# 3_-MCU.net
KiCad netlist of a schematic drawn in Altium Designer
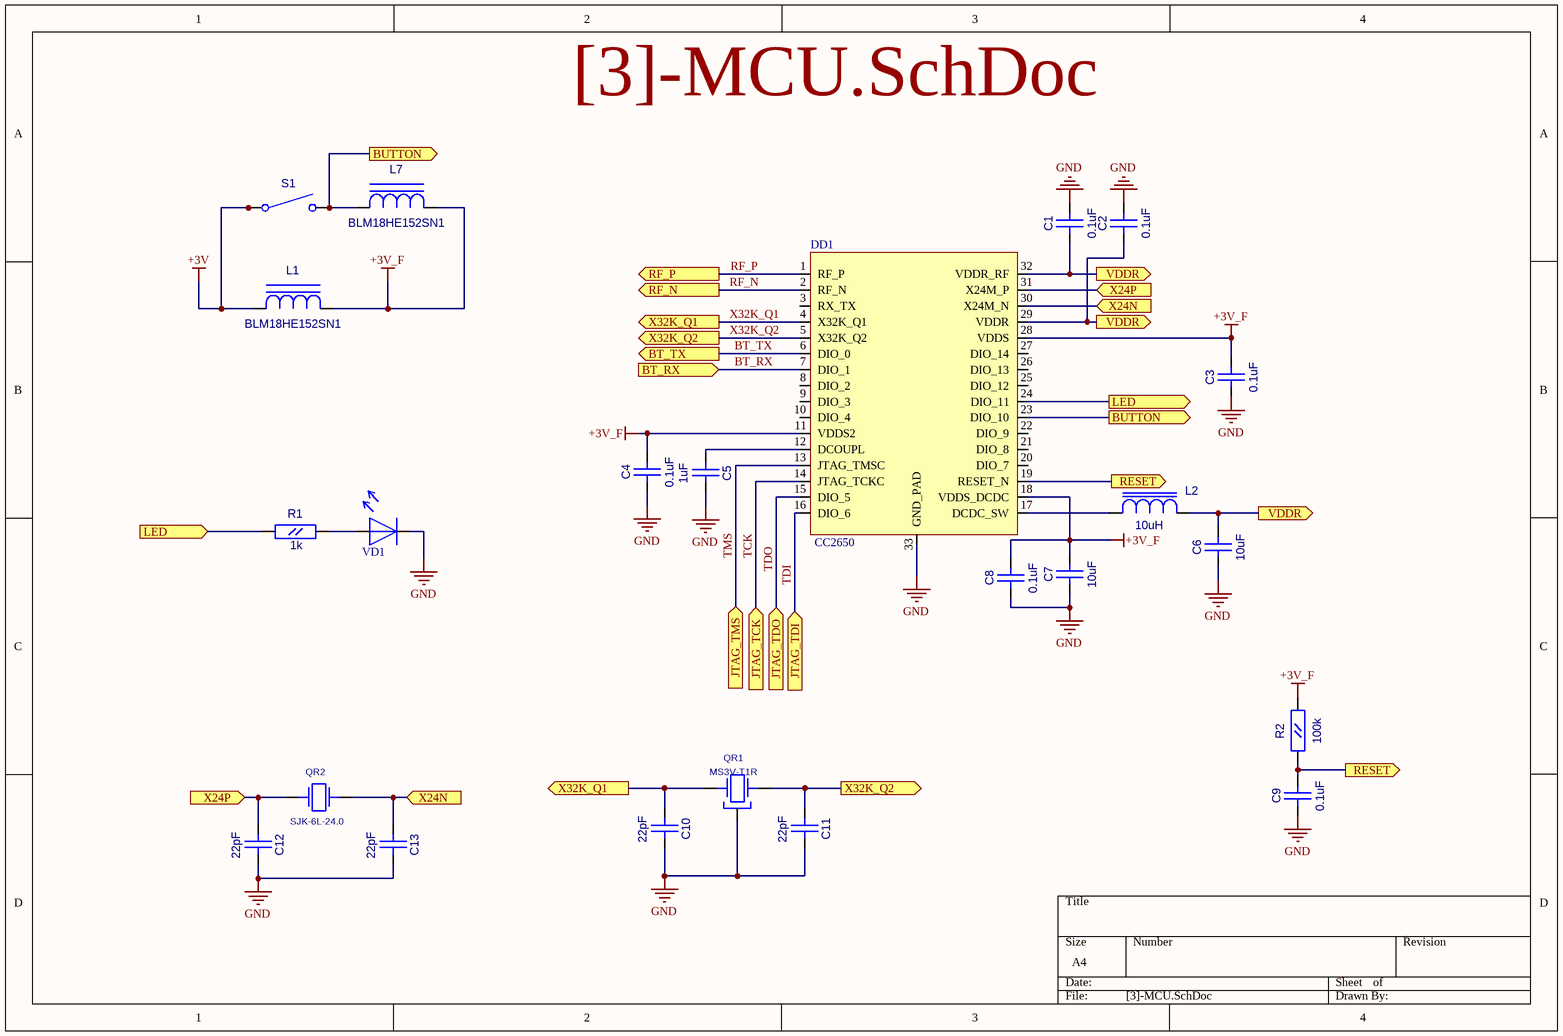
[diagram p0: [3]-MCU.SchDoc]

(export (version "E")
  (design (tool "Eeschema 10.0.6"))
  (components
    (comp (ref "C1")
      (value "0.1uF")
      (footprint "CC0603")
      (description "CC0603")
      (libsource (lib "gprs_modem_2") (part "CC0603"))
    )
    (comp (ref "C2")
      (value "0.1uF")
      (footprint "CC0603")
      (description "CC0603")
      (libsource (lib "gprs_modem_2") (part "CC0603"))
    )
    (comp (ref "C3")
      (value "0.1uF")
      (footprint "CC0603")
      (description "CC0603")
      (libsource (lib "gprs_modem_2") (part "CC0603"))
    )
    (comp (ref "C4")
      (value "0.1uF")
      (footprint "CC0603")
      (description "CC0603")
      (libsource (lib "gprs_modem_2") (part "CC0603"))
    )
    (comp (ref "C5")
      (value "1uF")
      (footprint "CC0603")
      (description "CC0603")
      (libsource (lib "gprs_modem_2") (part "CC0603"))
    )
    (comp (ref "C6")
      (value "10uF")
      (footprint "CC0805")
      (description "CC0805")
      (libsource (lib "gprs_modem_2") (part "CC0805"))
    )
    (comp (ref "C7")
      (value "10uF")
      (footprint "CC0805")
      (description "CC0805")
      (libsource (lib "gprs_modem_2") (part "CC0805"))
    )
    (comp (ref "C8")
      (value "0.1uF")
      (footprint "CC0603")
      (description "CC0603")
      (libsource (lib "gprs_modem_2") (part "CC0603"))
    )
    (comp (ref "C9")
      (value "0.1uF")
      (footprint "CC0603")
      (description "CC0603")
      (libsource (lib "gprs_modem_2") (part "CC0603"))
    )
    (comp (ref "C10")
      (value "22pF")
      (footprint "CC0603")
      (description "CC0603")
      (libsource (lib "gprs_modem_2") (part "CC0603"))
    )
    (comp (ref "C11")
      (value "22pF")
      (footprint "CC0603")
      (description "CC0603")
      (libsource (lib "gprs_modem_2") (part "CC0603"))
    )
    (comp (ref "C12")
      (value "22pF")
      (footprint "CC0603")
      (description "CC0603")
      (libsource (lib "gprs_modem_2") (part "CC0603"))
    )
    (comp (ref "C13")
      (value "22pF")
      (footprint "CC0603")
      (description "CC0603")
      (libsource (lib "gprs_modem_2") (part "CC0603"))
    )
    (comp (ref "DD1")
      (value "CC2650")
      (footprint "QFN32_TI")
      (description "CC2650RHBT")
      (libsource (lib "gprs_modem_2") (part "CC2650RHB"))
    )
    (comp (ref "L1")
      (value "BLM18HE152SN1")
      (footprint "L0603")
      (description "L0603")
      (libsource (lib "gprs_modem_2") (part "L0603"))
    )
    (comp (ref "L2")
      (value "10uH")
      (footprint "RC0805")
      (description "L0805")
      (libsource (lib "gprs_modem_2") (part "L0805"))
    )
    (comp (ref "L7")
      (value "BLM18HE152SN1")
      (footprint "L0603")
      (description "L0603")
      (libsource (lib "gprs_modem_2") (part "L0603"))
    )
    (comp (ref "QR1")
      (value "MS3V-T1R")
      (footprint "MS3V-T1R")
      (description "CRYSTAL_32768 Hz")
      (libsource (lib "gprs_modem_2") (part "MS3V-T1R"))
    )
    (comp (ref "QR2")
      (value "SJK-6L-24.0")
      (footprint "AC5032_2")
      (description "AC5032/2")
      (libsource (lib "gprs_modem_2") (part "AC5032_2"))
    )
    (comp (ref "R1")
      (value "1k")
      (footprint "RC0603")
      (description "RC0603")
      (libsource (lib "fizik_lib") (part "RC0603"))
    )
    (comp (ref "R2")
      (value "100k")
      (footprint "RC0603")
      (description "RC0603")
      (libsource (lib "gprs_modem_2") (part "RC0603"))
    )
    (comp (ref "S1")
      (value "IT-1147")
      (footprint "IT-1147")
      (description "Switch, Single Pole, Single Throw, Normally Open")
      (libsource (lib "fizik_lib") (part "IT-1147"))
    )
    (comp (ref "VD1")
      (value "LED_0805")
      (footprint "LED0805")
      (libsource (lib "fizik_lib") (part "LED_0805"))
    )
  )
  (nets
    (net (code "1") (name "+3V") (class "Default")
      (node (ref "L1") (pin "1") (pinfunction "A_1") (pintype "passive"))
      (node (ref "S1") (pin "1") (pinfunction "C1_1") (pintype "passive"))
      (node (ref "S1") (pin "2") (pintype "passive"))
    )
    (net (code "2") (name "+3V_F") (class "Default")
      (node (ref "C3") (pin "2") (pinfunction "B_2") (pintype "passive"))
      (node (ref "C4") (pin "2") (pinfunction "B_2") (pintype "passive"))
      (node (ref "C7") (pin "2") (pinfunction "B_2") (pintype "passive"))
      (node (ref "C8") (pin "2") (pinfunction "B_2") (pintype "passive"))
      (node (ref "DD1") (pin "11") (pinfunction "VDDS2_11") (pintype "passive"))
      (node (ref "DD1") (pin "18") (pinfunction "VDDS_DCDC_18") (pintype "passive"))
      (node (ref "DD1") (pin "28") (pinfunction "VDDS_28") (pintype "passive"))
      (node (ref "L1") (pin "2") (pinfunction "C_2") (pintype "passive"))
      (node (ref "L7") (pin "2") (pinfunction "C_2") (pintype "passive"))
      (node (ref "R2") (pin "2") (pinfunction "B_2") (pintype "passive"))
    )
    (net (code "3") (name "/BT_RX") (class "Default")
      (node (ref "DD1") (pin "7") (pinfunction "DIO_1_7") (pintype "passive"))
    )
    (net (code "4") (name "/BT_TX") (class "Default")
      (node (ref "DD1") (pin "6") (pinfunction "DIO_0_6") (pintype "passive"))
    )
    (net (code "5") (name "/BUTTON") (class "Default")
      (node (ref "DD1") (pin "23") (pinfunction "DIO_10_23") (pintype "passive"))
      (node (ref "L7") (pin "1") (pinfunction "A_1") (pintype "passive"))
      (node (ref "S1") (pin "3") (pinfunction "C2_3") (pintype "passive"))
      (node (ref "S1") (pin "4") (pintype "passive"))
    )
    (net (code "6") (name "/LED") (class "Default")
      (node (ref "DD1") (pin "24") (pinfunction "DIO_11_24") (pintype "passive"))
      (node (ref "R1") (pin "1") (pinfunction "A_1") (pintype "passive"))
    )
    (net (code "7") (name "/RESET") (class "Default")
      (node (ref "C9") (pin "2") (pinfunction "B_2") (pintype "passive"))
      (node (ref "DD1") (pin "19") (pinfunction "RESET_N_19") (pintype "passive"))
      (node (ref "R2") (pin "1") (pinfunction "A_1") (pintype "passive"))
    )
    (net (code "8") (name "/RF_N") (class "Default")
      (node (ref "DD1") (pin "2") (pinfunction "RF_N_2") (pintype "passive"))
    )
    (net (code "9") (name "/RF_P") (class "Default")
      (node (ref "DD1") (pin "1") (pinfunction "RF_P_1") (pintype "passive"))
    )
    (net (code "10") (name "/TCK") (class "Default")
      (node (ref "DD1") (pin "14") (pinfunction "JTAG_TCKC_14") (pintype "passive"))
    )
    (net (code "11") (name "/TDI") (class "Default")
      (node (ref "DD1") (pin "16") (pinfunction "DIO_6_16") (pintype "passive"))
    )
    (net (code "12") (name "/TDO") (class "Default")
      (node (ref "DD1") (pin "15") (pinfunction "DIO_5_15") (pintype "passive"))
    )
    (net (code "13") (name "/TMS") (class "Default")
      (node (ref "DD1") (pin "13") (pinfunction "JTAG_TMSC_13") (pintype "passive"))
    )
    (net (code "14") (name "/VDDR") (class "Default")
      (node (ref "C1") (pin "1") (pinfunction "A_1") (pintype "passive"))
      (node (ref "C2") (pin "1") (pinfunction "A_1") (pintype "passive"))
      (node (ref "C6") (pin "2") (pinfunction "B_2") (pintype "passive"))
      (node (ref "DD1") (pin "29") (pinfunction "VDDR_29") (pintype "passive"))
      (node (ref "DD1") (pin "32") (pinfunction "VDDR_RF_32") (pintype "passive"))
      (node (ref "L2") (pin "2") (pinfunction "B_2") (pintype "passive"))
    )
    (net (code "15") (name "/X24N") (class "Default")
      (node (ref "C13") (pin "1") (pinfunction "A_1") (pintype "passive"))
      (node (ref "DD1") (pin "30") (pinfunction "X24M_N_30") (pintype "passive"))
      (node (ref "QR2") (pin "2") (pintype "passive"))
    )
    (net (code "16") (name "/X24P") (class "Default")
      (node (ref "C12") (pin "1") (pinfunction "A_1") (pintype "passive"))
      (node (ref "DD1") (pin "31") (pinfunction "X24M_P_31") (pintype "passive"))
      (node (ref "QR2") (pin "1") (pintype "passive"))
    )
    (net (code "17") (name "/X32K_Q1") (class "Default")
      (node (ref "C10") (pin "1") (pinfunction "A_1") (pintype "passive"))
      (node (ref "DD1") (pin "4") (pinfunction "X32K_Q1_4") (pintype "passive"))
      (node (ref "QR1") (pin "2") (pinfunction "X2_2") (pintype "passive"))
    )
    (net (code "18") (name "/X32K_Q2") (class "Default")
      (node (ref "C11") (pin "1") (pinfunction "A_1") (pintype "passive"))
      (node (ref "DD1") (pin "5") (pinfunction "X32K_Q2_5") (pintype "passive"))
      (node (ref "QR1") (pin "1") (pinfunction "X1_1") (pintype "passive"))
    )
    (net (code "19") (name "GND") (class "Default")
      (node (ref "C1") (pin "2") (pinfunction "B_2") (pintype "passive"))
      (node (ref "C10") (pin "2") (pinfunction "B_2") (pintype "passive"))
      (node (ref "C11") (pin "2") (pinfunction "B_2") (pintype "passive"))
      (node (ref "C12") (pin "2") (pinfunction "B_2") (pintype "passive"))
      (node (ref "C13") (pin "2") (pinfunction "B_2") (pintype "passive"))
      (node (ref "C2") (pin "2") (pinfunction "B_2") (pintype "passive"))
      (node (ref "C3") (pin "1") (pinfunction "A_1") (pintype "passive"))
      (node (ref "C4") (pin "1") (pinfunction "A_1") (pintype "passive"))
      (node (ref "C5") (pin "2") (pinfunction "B_2") (pintype "passive"))
      (node (ref "C6") (pin "1") (pinfunction "A_1") (pintype "passive"))
      (node (ref "C7") (pin "1") (pinfunction "A_1") (pintype "passive"))
      (node (ref "C8") (pin "1") (pinfunction "A_1") (pintype "passive"))
      (node (ref "C9") (pin "1") (pinfunction "A_1") (pintype "passive"))
      (node (ref "DD1") (pin "33") (pinfunction "GND_PAD_33") (pintype "passive"))
      (node (ref "QR1") (pin "3") (pinfunction "3_3") (pintype "passive"))
      (node (ref "VD1") (pin "2") (pintype "passive"))
    )
    (net (code "20") (name "Net-(C5-A)") (class "Default")
      (node (ref "C5") (pin "1") (pinfunction "A_1") (pintype "passive"))
      (node (ref "DD1") (pin "12") (pinfunction "DCOUPL_12") (pintype "passive"))
    )
    (net (code "21") (name "Net-(DD1-DCDC_SW)") (class "Default")
      (node (ref "DD1") (pin "17") (pinfunction "DCDC_SW_17") (pintype "passive"))
      (node (ref "L2") (pin "1") (pinfunction "A_1") (pintype "passive"))
    )
    (net (code "22") (name "Net-(R1-B)") (class "Default")
      (node (ref "R1") (pin "2") (pinfunction "B_2") (pintype "passive"))
      (node (ref "VD1") (pin "1") (pintype "passive"))
    )
    (net (code "23") (name "unconnected-(DD1-DIO_2-Pad8)") (class "Default")
      (node (ref "DD1") (pin "8") (pinfunction "DIO_2_8") (pintype "passive"))
    )
    (net (code "24") (name "unconnected-(DD1-DIO_3-Pad9)") (class "Default")
      (node (ref "DD1") (pin "9") (pinfunction "DIO_3_9") (pintype "passive"))
    )
    (net (code "25") (name "unconnected-(DD1-DIO_4-Pad10)") (class "Default")
      (node (ref "DD1") (pin "10") (pinfunction "DIO_4_10") (pintype "passive"))
    )
    (net (code "26") (name "unconnected-(DD1-DIO_7-Pad20)") (class "Default")
      (node (ref "DD1") (pin "20") (pinfunction "DIO_7_20") (pintype "passive"))
    )
    (net (code "27") (name "unconnected-(DD1-DIO_8-Pad21)") (class "Default")
      (node (ref "DD1") (pin "21") (pinfunction "DIO_8_21") (pintype "passive"))
    )
    (net (code "28") (name "unconnected-(DD1-DIO_9-Pad22)") (class "Default")
      (node (ref "DD1") (pin "22") (pinfunction "DIO_9_22") (pintype "passive"))
    )
    (net (code "29") (name "unconnected-(DD1-DIO_12-Pad25)") (class "Default")
      (node (ref "DD1") (pin "25") (pinfunction "DIO_12_25") (pintype "passive"))
    )
    (net (code "30") (name "unconnected-(DD1-DIO_13-Pad26)") (class "Default")
      (node (ref "DD1") (pin "26") (pinfunction "DIO_13_26") (pintype "passive"))
    )
    (net (code "31") (name "unconnected-(DD1-DIO_14-Pad27)") (class "Default")
      (node (ref "DD1") (pin "27") (pinfunction "DIO_14_27") (pintype "passive"))
    )
    (net (code "32") (name "unconnected-(DD1-RX_TX-Pad3)") (class "Default")
      (node (ref "DD1") (pin "3") (pinfunction "RX_TX_3") (pintype "passive"))
    )
  )
)
